# Physical_Computing_Bridge_V6.net
KiCad netlist of a schematic drawn in EAGLE
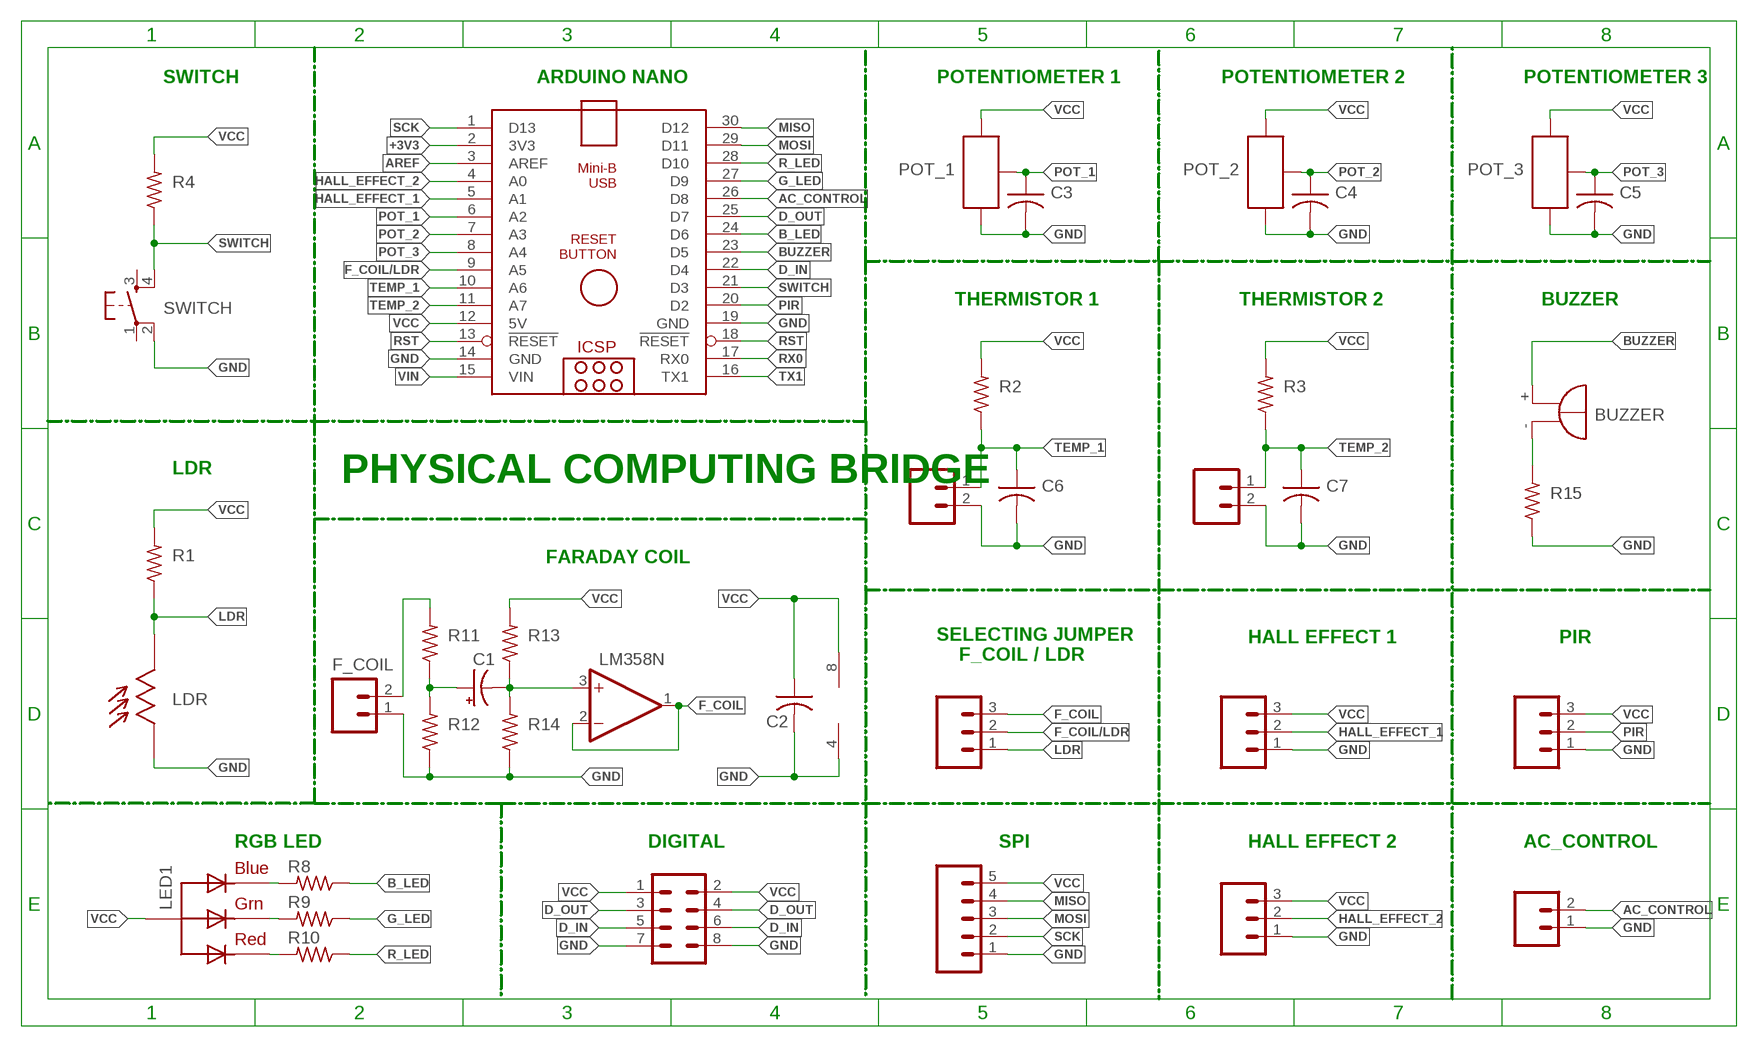
[diagram p0: schematic, sheet 1]

(export (version "E")
  (design (tool "Eeschema 10.0.6"))
  (components
    (comp (ref "AC_CONTROL")
      (value "CONN_02POLAR")
      (footprint "eagle-import:MOLEX-1X2")
      (libsource (lib "eagle-import") (part "CONN_02POLAR"))
    )
    (comp (ref "ARDUINO_NANO1")
      (value "ARDUINO_NANO")
      (footprint "eagle-import:ARDUINO_NANO")
      (libsource (lib "eagle-import") (part "ARDUINO_NANO"))
    )
    (comp (ref "BUZZER")
      (value "BUZZER")
      (footprint "eagle-import:F_TMB")
      (libsource (lib "eagle-import") (part "BUZZER"))
    )
    (comp (ref "C1")
      (value "CPOL-USE2.5-7")
      (footprint "eagle-import:E2,5-7")
      (libsource (lib "eagle-import") (part "CPOL-USE2.5-7"))
    )
    (comp (ref "C2")
      (value "C-US025-025X050")
      (footprint "eagle-import:C025-025X050")
      (libsource (lib "eagle-import") (part "C-US025-025X050"))
    )
    (comp (ref "C3")
      (value "C-US025-025X050")
      (footprint "eagle-import:C025-025X050")
      (libsource (lib "eagle-import") (part "C-US025-025X050"))
    )
    (comp (ref "C4")
      (value "C-US025-025X050")
      (footprint "eagle-import:C025-025X050")
      (libsource (lib "eagle-import") (part "C-US025-025X050"))
    )
    (comp (ref "C5")
      (value "C-US025-025X050")
      (footprint "eagle-import:C025-025X050")
      (libsource (lib "eagle-import") (part "C-US025-025X050"))
    )
    (comp (ref "C6")
      (value "C-US025-025X050")
      (footprint "eagle-import:C025-025X050")
      (libsource (lib "eagle-import") (part "C-US025-025X050"))
    )
    (comp (ref "C7")
      (value "C-US025-025X050")
      (footprint "eagle-import:C025-025X050")
      (libsource (lib "eagle-import") (part "C-US025-025X050"))
    )
    (comp (ref "DIGITAL")
      (value "CONN_04X2")
      (footprint "eagle-import:2X4")
      (libsource (lib "eagle-import") (part "CONN_04X2"))
    )
    (comp (ref "F_COIL")
      (value "CONN_02POLAR")
      (footprint "eagle-import:MOLEX-1X2")
      (libsource (lib "eagle-import") (part "CONN_02POLAR"))
    )
    (comp (ref "HALL_EFFECT_1")
      (value "CONN_03POLAR")
      (footprint "eagle-import:MOLEX-1X3")
      (libsource (lib "eagle-import") (part "CONN_03POLAR"))
    )
    (comp (ref "HALL_EFFECT_2")
      (value "CONN_03POLAR")
      (footprint "eagle-import:MOLEX-1X3")
      (libsource (lib "eagle-import") (part "CONN_03POLAR"))
    )
    (comp (ref "IC1")
      (value "LM358N")
      (footprint "eagle-import:DIL08")
      (libsource (lib "eagle-import") (part "LM358N"))
    )
    (comp (ref "LDR")
      (value "CDSLDR3MM")
      (footprint "eagle-import:LDR3MM")
      (libsource (lib "eagle-import") (part "CDSLDR3MM"))
    )
    (comp (ref "LED1")
      (value "RGBLED_CA-5MM")
      (footprint "eagle-import:LED5MMRGB")
      (libsource (lib "eagle-import") (part "RGBLED_CA-5MM"))
    )
    (comp (ref "PIR")
      (value "CONN_03POLAR")
      (footprint "eagle-import:MOLEX-1X3")
      (libsource (lib "eagle-import") (part "CONN_03POLAR"))
    )
    (comp (ref "POT_1")
      (value "POTNORMAL")
      (footprint "eagle-import:RJ9W")
      (libsource (lib "eagle-import") (part "POTNORMAL"))
    )
    (comp (ref "POT_2")
      (value "POTNORMAL")
      (footprint "eagle-import:RJ9W")
      (libsource (lib "eagle-import") (part "POTNORMAL"))
    )
    (comp (ref "POT_3")
      (value "POTNORMAL")
      (footprint "eagle-import:RJ9W")
      (libsource (lib "eagle-import") (part "POTNORMAL"))
    )
    (comp (ref "R1")
      (value "R-US_0204/7")
      (footprint "eagle-import:0204_7")
      (libsource (lib "eagle-import") (part "R-US_0204/7"))
    )
    (comp (ref "R2")
      (value "R-US_0204/7")
      (footprint "eagle-import:0204_7")
      (libsource (lib "eagle-import") (part "R-US_0204/7"))
    )
    (comp (ref "R3")
      (value "R-US_0204/7")
      (footprint "eagle-import:0204_7")
      (libsource (lib "eagle-import") (part "R-US_0204/7"))
    )
    (comp (ref "R4")
      (value "R-US_0204/7")
      (footprint "eagle-import:0204_7")
      (libsource (lib "eagle-import") (part "R-US_0204/7"))
    )
    (comp (ref "R8")
      (value "R-US_0204/7")
      (footprint "eagle-import:0204_7")
      (libsource (lib "eagle-import") (part "R-US_0204/7"))
    )
    (comp (ref "R9")
      (value "R-US_0204/7")
      (footprint "eagle-import:0204_7")
      (libsource (lib "eagle-import") (part "R-US_0204/7"))
    )
    (comp (ref "R10")
      (value "R-US_0204/7")
      (footprint "eagle-import:0204_7")
      (libsource (lib "eagle-import") (part "R-US_0204/7"))
    )
    (comp (ref "R11")
      (value "R-US_0204/7")
      (footprint "eagle-import:0204_7")
      (libsource (lib "eagle-import") (part "R-US_0204/7"))
    )
    (comp (ref "R12")
      (value "R-US_0204/7")
      (footprint "eagle-import:0204_7")
      (libsource (lib "eagle-import") (part "R-US_0204/7"))
    )
    (comp (ref "R13")
      (value "R-US_0204/7")
      (footprint "eagle-import:0204_7")
      (libsource (lib "eagle-import") (part "R-US_0204/7"))
    )
    (comp (ref "R14")
      (value "R-US_0204/7")
      (footprint "eagle-import:0204_7")
      (libsource (lib "eagle-import") (part "R-US_0204/7"))
    )
    (comp (ref "R15")
      (value "R-US_0204/7")
      (footprint "eagle-import:0204_7")
      (libsource (lib "eagle-import") (part "R-US_0204/7"))
    )
    (comp (ref "SELECTINGJUMPER")
      (value "CONN_03LONGPADS")
      (footprint "eagle-import:1X03_LONGPADS")
      (libsource (lib "eagle-import") (part "CONN_03LONGPADS"))
    )
    (comp (ref "SPI")
      (value "CONN_05PTH_LONGPADS")
      (footprint "eagle-import:1X05_LONGPADS")
      (libsource (lib "eagle-import") (part "CONN_05PTH_LONGPADS"))
    )
    (comp (ref "SWITCH")
      (value "OMRON_SWITCH_40-XX")
      (footprint "eagle-import:B3F-40XX")
      (libsource (lib "eagle-import") (part "OMRON_SWITCH_40-XX"))
    )
    (comp (ref "THERMISTOR1")
      (value "CONN_02POLAR")
      (footprint "eagle-import:MOLEX-1X2")
      (libsource (lib "eagle-import") (part "CONN_02POLAR"))
    )
    (comp (ref "THERMISTOR2")
      (value "CONN_02POLAR")
      (footprint "eagle-import:MOLEX-1X2")
      (libsource (lib "eagle-import") (part "CONN_02POLAR"))
    )
  )
  (nets
    (net (code "1") (name "+3V3") (class "Default")
      (node (ref "ARDUINO_NANO1") (pin "2") (pinfunction "3V3_2") (pintype "output"))
    )
    (net (code "2") (name "AC_CONTROL") (class "Default")
      (node (ref "AC_CONTROL") (pin "2") (pinfunction "2_2") (pintype "passive"))
      (node (ref "ARDUINO_NANO1") (pin "26") (pinfunction "D8_26") (pintype "bidirectional"))
    )
    (net (code "3") (name "AREF") (class "Default")
      (node (ref "ARDUINO_NANO1") (pin "3") (pinfunction "AREF_3") (pintype "input"))
    )
    (net (code "4") (name "BUZZER") (class "Default")
      (node (ref "ARDUINO_NANO1") (pin "23") (pinfunction "D5_23") (pintype "bidirectional"))
      (node (ref "BUZZER") (pin "+") (pinfunction "+_+") (pintype "passive"))
    )
    (net (code "5") (name "B_LED") (class "Default")
      (node (ref "ARDUINO_NANO1") (pin "24") (pinfunction "D6_24") (pintype "bidirectional"))
      (node (ref "R8") (pin "1") (pinfunction "1_1") (pintype "passive"))
    )
    (net (code "6") (name "D_IN") (class "Default")
      (node (ref "ARDUINO_NANO1") (pin "22") (pinfunction "D4_22") (pintype "bidirectional"))
      (node (ref "DIGITAL") (pin "5") (pinfunction "5_5") (pintype "passive"))
      (node (ref "DIGITAL") (pin "6") (pinfunction "6_6") (pintype "passive"))
    )
    (net (code "7") (name "D_OUT") (class "Default")
      (node (ref "ARDUINO_NANO1") (pin "25") (pinfunction "D7_25") (pintype "bidirectional"))
      (node (ref "DIGITAL") (pin "3") (pinfunction "3_3") (pintype "passive"))
      (node (ref "DIGITAL") (pin "4") (pinfunction "4_4") (pintype "passive"))
    )
    (net (code "8") (name "F_COIL") (class "Default")
      (node (ref "IC1") (pin "1") (pinfunction "OUT_1") (pintype "output"))
      (node (ref "IC1") (pin "2") (pinfunction "-IN_2") (pintype "input"))
      (node (ref "SELECTINGJUMPER") (pin "3") (pinfunction "3_3") (pintype "passive"))
    )
    (net (code "9") (name "F_COIL{slash}LDR") (class "Default")
      (node (ref "ARDUINO_NANO1") (pin "9") (pinfunction "A5_9") (pintype "bidirectional"))
      (node (ref "SELECTINGJUMPER") (pin "2") (pinfunction "2_2") (pintype "passive"))
    )
    (net (code "10") (name "GND") (class "Default")
      (node (ref "AC_CONTROL") (pin "1") (pinfunction "1_1") (pintype "passive"))
      (node (ref "ARDUINO_NANO1") (pin "14") (pinfunction "GND_14") (pintype "power_in"))
      (node (ref "ARDUINO_NANO1") (pin "19") (pinfunction "GND_19") (pintype "power_in"))
      (node (ref "C2") (pin "2") (pinfunction "2_2") (pintype "passive"))
      (node (ref "C3") (pin "2") (pinfunction "2_2") (pintype "passive"))
      (node (ref "C4") (pin "2") (pinfunction "2_2") (pintype "passive"))
      (node (ref "C5") (pin "2") (pinfunction "2_2") (pintype "passive"))
      (node (ref "C6") (pin "2") (pinfunction "2_2") (pintype "passive"))
      (node (ref "C7") (pin "2") (pinfunction "2_2") (pintype "passive"))
      (node (ref "DIGITAL") (pin "7") (pinfunction "7_7") (pintype "passive"))
      (node (ref "DIGITAL") (pin "8") (pinfunction "8_8") (pintype "passive"))
      (node (ref "F_COIL") (pin "1") (pinfunction "1_1") (pintype "passive"))
      (node (ref "HALL_EFFECT_1") (pin "1") (pinfunction "1_1") (pintype "passive"))
      (node (ref "HALL_EFFECT_2") (pin "1") (pinfunction "1_1") (pintype "passive"))
      (node (ref "IC1") (pin "4") (pinfunction "V-_4") (pintype "power_in"))
      (node (ref "LDR") (pin "P$1") (pinfunction "P$1_P$1") (pintype "bidirectional"))
      (node (ref "PIR") (pin "1") (pinfunction "1_1") (pintype "passive"))
      (node (ref "POT_1") (pin "E") (pinfunction "E_E") (pintype "passive"))
      (node (ref "POT_2") (pin "E") (pinfunction "E_E") (pintype "passive"))
      (node (ref "POT_3") (pin "E") (pinfunction "E_E") (pintype "passive"))
      (node (ref "R12") (pin "1") (pinfunction "1_1") (pintype "passive"))
      (node (ref "R14") (pin "1") (pinfunction "1_1") (pintype "passive"))
      (node (ref "R15") (pin "1") (pinfunction "1_1") (pintype "passive"))
      (node (ref "SPI") (pin "1") (pinfunction "1_1") (pintype "passive"))
      (node (ref "SWITCH") (pin "2") (pinfunction "P1_2") (pintype "passive"))
      (node (ref "THERMISTOR1") (pin "2") (pinfunction "2_2") (pintype "passive"))
      (node (ref "THERMISTOR2") (pin "2") (pinfunction "2_2") (pintype "passive"))
    )
    (net (code "11") (name "G_LED") (class "Default")
      (node (ref "ARDUINO_NANO1") (pin "27") (pinfunction "D9_27") (pintype "bidirectional"))
      (node (ref "R9") (pin "1") (pinfunction "1_1") (pintype "passive"))
    )
    (net (code "12") (name "HALL_EFFECT_1") (class "Default")
      (node (ref "ARDUINO_NANO1") (pin "5") (pinfunction "A1_5") (pintype "bidirectional"))
      (node (ref "HALL_EFFECT_1") (pin "2") (pinfunction "2_2") (pintype "passive"))
    )
    (net (code "13") (name "HALL_EFFECT_2") (class "Default")
      (node (ref "ARDUINO_NANO1") (pin "4") (pinfunction "A0_4") (pintype "bidirectional"))
      (node (ref "HALL_EFFECT_2") (pin "2") (pinfunction "2_2") (pintype "passive"))
    )
    (net (code "14") (name "LDR") (class "Default")
      (node (ref "LDR") (pin "P$2") (pinfunction "P$2_P$2") (pintype "bidirectional"))
      (node (ref "R1") (pin "1") (pinfunction "1_1") (pintype "passive"))
      (node (ref "SELECTINGJUMPER") (pin "1") (pinfunction "1_1") (pintype "passive"))
    )
    (net (code "15") (name "MISO") (class "Default")
      (node (ref "ARDUINO_NANO1") (pin "30") (pinfunction "D12_30") (pintype "bidirectional"))
      (node (ref "SPI") (pin "4") (pinfunction "4_4") (pintype "passive"))
    )
    (net (code "16") (name "MOSI") (class "Default")
      (node (ref "ARDUINO_NANO1") (pin "29") (pinfunction "D11_29") (pintype "bidirectional"))
      (node (ref "SPI") (pin "3") (pinfunction "3_3") (pintype "passive"))
    )
    (net (code "17") (name "Net-(BUZZER-Pad-)") (class "Default")
      (node (ref "BUZZER") (pin "-") (pinfunction "-_-") (pintype "passive"))
      (node (ref "R15") (pin "2") (pinfunction "2_2") (pintype "passive"))
    )
    (net (code "18") (name "Net-(C1-Pad+)") (class "Default")
      (node (ref "C1") (pin "+") (pinfunction "+_+") (pintype "passive"))
      (node (ref "R11") (pin "1") (pinfunction "1_1") (pintype "passive"))
      (node (ref "R12") (pin "2") (pinfunction "2_2") (pintype "passive"))
    )
    (net (code "19") (name "Net-(F_COIL-Pad2)") (class "Default")
      (node (ref "F_COIL") (pin "2") (pinfunction "2_2") (pintype "passive"))
      (node (ref "R11") (pin "2") (pinfunction "2_2") (pintype "passive"))
    )
    (net (code "20") (name "Net-(IC1A-+IN)") (class "Default")
      (node (ref "C1") (pin "-") (pinfunction "-_-") (pintype "passive"))
      (node (ref "IC1") (pin "3") (pinfunction "+IN_3") (pintype "input"))
      (node (ref "R13") (pin "1") (pinfunction "1_1") (pintype "passive"))
      (node (ref "R14") (pin "2") (pinfunction "2_2") (pintype "passive"))
    )
    (net (code "21") (name "Net-(LED1-BLUE)") (class "Default")
      (node (ref "LED1") (pin "4") (pinfunction "BLUE_4") (pintype "bidirectional"))
      (node (ref "R8") (pin "2") (pinfunction "2_2") (pintype "passive"))
    )
    (net (code "22") (name "Net-(LED1-GREEN)") (class "Default")
      (node (ref "LED1") (pin "3") (pinfunction "GREEN_3") (pintype "bidirectional"))
      (node (ref "R9") (pin "2") (pinfunction "2_2") (pintype "passive"))
    )
    (net (code "23") (name "Net-(LED1-RED)") (class "Default")
      (node (ref "LED1") (pin "1") (pinfunction "RED_1") (pintype "bidirectional"))
      (node (ref "R10") (pin "2") (pinfunction "2_2") (pintype "passive"))
    )
    (net (code "24") (name "PIR") (class "Default")
      (node (ref "ARDUINO_NANO1") (pin "20") (pinfunction "D2_20") (pintype "bidirectional"))
      (node (ref "PIR") (pin "2") (pinfunction "2_2") (pintype "passive"))
    )
    (net (code "25") (name "POT_1") (class "Default")
      (node (ref "ARDUINO_NANO1") (pin "6") (pinfunction "A2_6") (pintype "bidirectional"))
      (node (ref "C3") (pin "1") (pinfunction "1_1") (pintype "passive"))
      (node (ref "POT_1") (pin "S") (pinfunction "S_S") (pintype "passive"))
    )
    (net (code "26") (name "POT_2") (class "Default")
      (node (ref "ARDUINO_NANO1") (pin "7") (pinfunction "A3_7") (pintype "bidirectional"))
      (node (ref "C4") (pin "1") (pinfunction "1_1") (pintype "passive"))
      (node (ref "POT_2") (pin "S") (pinfunction "S_S") (pintype "passive"))
    )
    (net (code "27") (name "POT_3") (class "Default")
      (node (ref "ARDUINO_NANO1") (pin "8") (pinfunction "A4_8") (pintype "bidirectional"))
      (node (ref "C5") (pin "1") (pinfunction "1_1") (pintype "passive"))
      (node (ref "POT_3") (pin "S") (pinfunction "S_S") (pintype "passive"))
    )
    (net (code "28") (name "RST") (class "Default")
      (node (ref "ARDUINO_NANO1") (pin "13") (pinfunction "~{RESET}_13") (pintype "input"))
      (node (ref "ARDUINO_NANO1") (pin "18") (pinfunction "~{RESET}_18") (pintype "input"))
    )
    (net (code "29") (name "RX0") (class "Default")
      (node (ref "ARDUINO_NANO1") (pin "17") (pinfunction "RX0_17") (pintype "bidirectional"))
    )
    (net (code "30") (name "R_LED") (class "Default")
      (node (ref "ARDUINO_NANO1") (pin "28") (pinfunction "D10_28") (pintype "bidirectional"))
      (node (ref "R10") (pin "1") (pinfunction "1_1") (pintype "passive"))
    )
    (net (code "31") (name "SCK") (class "Default")
      (node (ref "ARDUINO_NANO1") (pin "1") (pinfunction "D13_1") (pintype "bidirectional"))
      (node (ref "SPI") (pin "2") (pinfunction "2_2") (pintype "passive"))
    )
    (net (code "32") (name "SWITCH") (class "Default")
      (node (ref "ARDUINO_NANO1") (pin "21") (pinfunction "D3_21") (pintype "bidirectional"))
      (node (ref "R4") (pin "1") (pinfunction "1_1") (pintype "passive"))
      (node (ref "SWITCH") (pin "4") (pinfunction "S1_4") (pintype "passive"))
    )
    (net (code "33") (name "TEMP_1") (class "Default")
      (node (ref "ARDUINO_NANO1") (pin "10") (pinfunction "A6_10") (pintype "bidirectional"))
      (node (ref "C6") (pin "1") (pinfunction "1_1") (pintype "passive"))
      (node (ref "R2") (pin "1") (pinfunction "1_1") (pintype "passive"))
      (node (ref "THERMISTOR1") (pin "1") (pinfunction "1_1") (pintype "passive"))
    )
    (net (code "34") (name "TEMP_2") (class "Default")
      (node (ref "ARDUINO_NANO1") (pin "11") (pinfunction "A7_11") (pintype "bidirectional"))
      (node (ref "C7") (pin "1") (pinfunction "1_1") (pintype "passive"))
      (node (ref "R3") (pin "1") (pinfunction "1_1") (pintype "passive"))
      (node (ref "THERMISTOR2") (pin "1") (pinfunction "1_1") (pintype "passive"))
    )
    (net (code "35") (name "TX1") (class "Default")
      (node (ref "ARDUINO_NANO1") (pin "16") (pinfunction "TX1_16") (pintype "bidirectional"))
    )
    (net (code "36") (name "VCC") (class "Default")
      (node (ref "ARDUINO_NANO1") (pin "12") (pinfunction "5V_12") (pintype "power_in"))
      (node (ref "C2") (pin "1") (pinfunction "1_1") (pintype "passive"))
      (node (ref "DIGITAL") (pin "1") (pinfunction "1_1") (pintype "passive"))
      (node (ref "DIGITAL") (pin "2") (pinfunction "2_2") (pintype "passive"))
      (node (ref "HALL_EFFECT_1") (pin "3") (pinfunction "3_3") (pintype "passive"))
      (node (ref "HALL_EFFECT_2") (pin "3") (pinfunction "3_3") (pintype "passive"))
      (node (ref "IC1") (pin "8") (pinfunction "V+_8") (pintype "power_in"))
      (node (ref "LED1") (pin "2") (pinfunction "VCC_2") (pintype "bidirectional"))
      (node (ref "PIR") (pin "3") (pinfunction "3_3") (pintype "passive"))
      (node (ref "POT_1") (pin "A") (pinfunction "A_A") (pintype "passive"))
      (node (ref "POT_2") (pin "A") (pinfunction "A_A") (pintype "passive"))
      (node (ref "POT_3") (pin "A") (pinfunction "A_A") (pintype "passive"))
      (node (ref "R1") (pin "2") (pinfunction "2_2") (pintype "passive"))
      (node (ref "R13") (pin "2") (pinfunction "2_2") (pintype "passive"))
      (node (ref "R2") (pin "2") (pinfunction "2_2") (pintype "passive"))
      (node (ref "R3") (pin "2") (pinfunction "2_2") (pintype "passive"))
      (node (ref "R4") (pin "2") (pinfunction "2_2") (pintype "passive"))
      (node (ref "SPI") (pin "5") (pinfunction "5_5") (pintype "passive"))
    )
    (net (code "37") (name "VIN") (class "Default")
      (node (ref "ARDUINO_NANO1") (pin "15") (pinfunction "VIN_15") (pintype "power_in"))
    )
    (net (code "38") (name "unconnected-(SWITCH-P-Pad1)") (class "Default")
      (node (ref "SWITCH") (pin "1") (pinfunction "P_1") (pintype "passive"))
    )
    (net (code "39") (name "unconnected-(SWITCH-S-Pad3)") (class "Default")
      (node (ref "SWITCH") (pin "3") (pinfunction "S_3") (pintype "passive"))
    )
  )
)
